# untitled.net
KiCad netlist of a schematic drawn in EAGLE
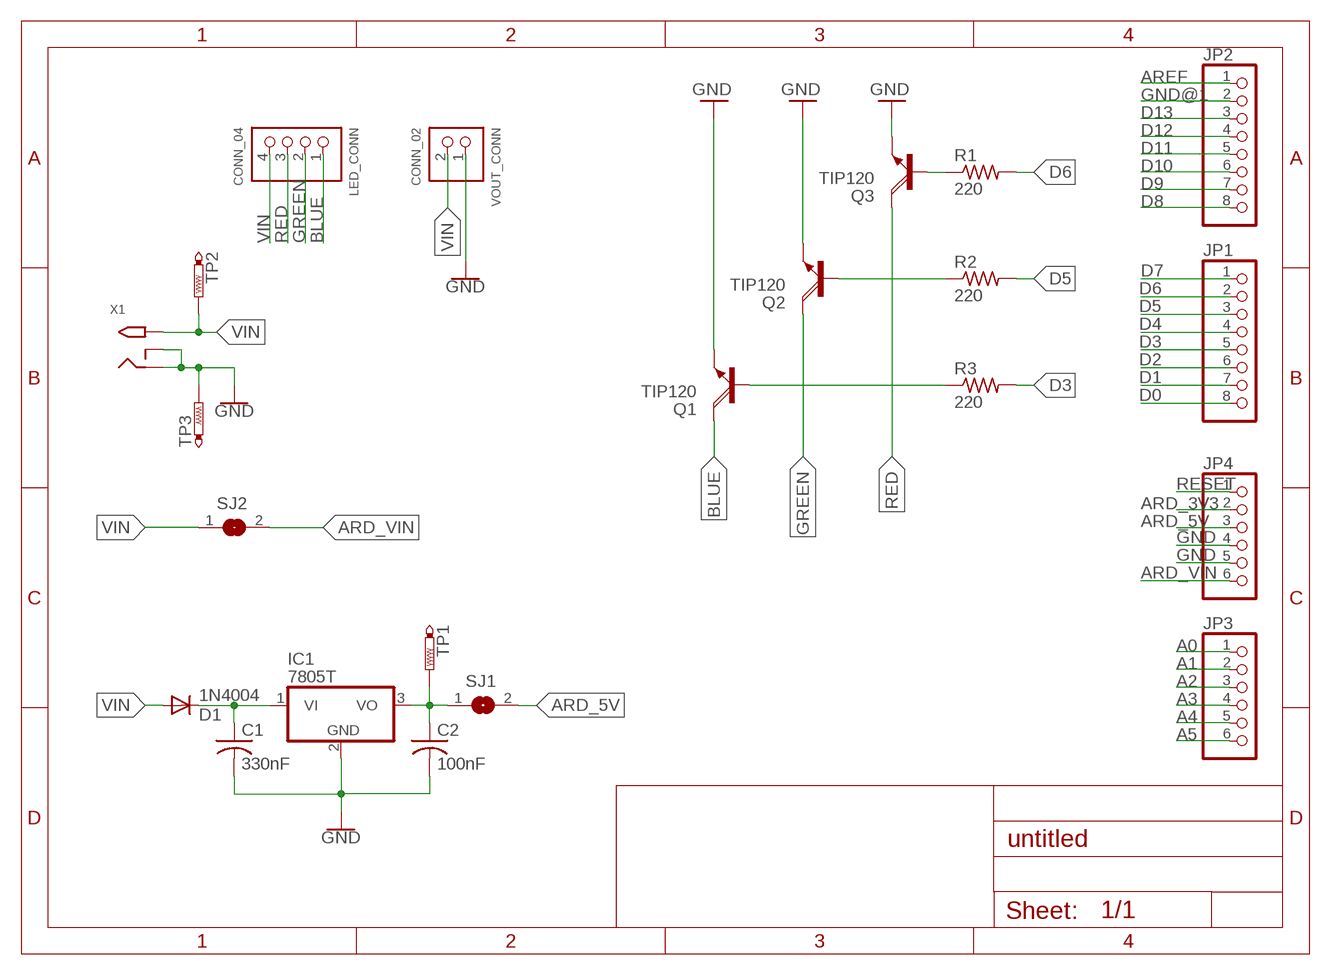
[diagram p0: schematic, sheet 1]

(export (version "E")
  (design (tool "Eeschema 10.0.6"))
  (components
    (comp (ref "C1")
      (value "330nF")
      (footprint "eagle-import:C050-035X075")
      (libsource (lib "eagle-import") (part "C-US050-035X075"))
    )
    (comp (ref "C2")
      (value "100nF")
      (footprint "eagle-import:C050-035X075")
      (libsource (lib "eagle-import") (part "C-US050-035X075"))
    )
    (comp (ref "D1")
      (value "1N4004")
      (footprint "eagle-import:DO41-10")
      (libsource (lib "eagle-import") (part "1N4004"))
    )
    (comp (ref "IC1")
      (value "7805T")
      (footprint "eagle-import:TO220H")
      (libsource (lib "eagle-import") (part "78T05"))
    )
    (comp (ref "JP1")
      (value "PINHD-1X8")
      (footprint "eagle-import:1X08")
      (libsource (lib "eagle-import") (part "PINHD-1X8"))
    )
    (comp (ref "JP2")
      (value "PINHD-1X8")
      (footprint "eagle-import:1X08")
      (libsource (lib "eagle-import") (part "PINHD-1X8"))
    )
    (comp (ref "JP3")
      (value "PINHD-1X6")
      (footprint "eagle-import:1X06")
      (libsource (lib "eagle-import") (part "PINHD-1X6"))
    )
    (comp (ref "JP4")
      (value "PINHD-1X6")
      (footprint "eagle-import:1X06")
      (libsource (lib "eagle-import") (part "PINHD-1X6"))
    )
    (comp (ref "LED_CONN")
      (value "CONN_04")
      (footprint "eagle-import:SCREWTERMINAL-5MM-4")
      (libsource (lib "eagle-import") (part "CONN_04"))
    )
    (comp (ref "Q1")
      (value "TIP120")
      (footprint "eagle-import:TO220AH")
      (libsource (lib "eagle-import") (part "TIP120"))
    )
    (comp (ref "Q2")
      (value "TIP120")
      (footprint "eagle-import:TO220AH")
      (libsource (lib "eagle-import") (part "TIP120"))
    )
    (comp (ref "Q3")
      (value "TIP120")
      (footprint "eagle-import:TO220AH")
      (libsource (lib "eagle-import") (part "TIP120"))
    )
    (comp (ref "R1")
      (value "220")
      (footprint "eagle-import:0207_9")
      (libsource (lib "eagle-import") (part "R-US_0207/9"))
    )
    (comp (ref "R2")
      (value "220")
      (footprint "eagle-import:0207_9")
      (libsource (lib "eagle-import") (part "R-US_0207/9"))
    )
    (comp (ref "R3")
      (value "220")
      (footprint "eagle-import:0207_9")
      (libsource (lib "eagle-import") (part "R-US_0207/9"))
    )
    (comp (ref "SJ1") (value "SJ") (footprint "eagle-import:SJ") (libsource (lib "eagle-import") (part "SJ")))
    (comp (ref "SJ2") (value "SJ") (footprint "eagle-import:SJ") (libsource (lib "eagle-import") (part "SJ")))
    (comp (ref "TP1")
      (value "PTR1B1,27")
      (footprint "eagle-import:B1,27")
      (libsource (lib "eagle-import") (part "PTR1B1,27"))
    )
    (comp (ref "TP2")
      (value "PTR1B1,27")
      (footprint "eagle-import:B1,27")
      (libsource (lib "eagle-import") (part "PTR1B1,27"))
    )
    (comp (ref "TP3")
      (value "PTR1B1,27")
      (footprint "eagle-import:B1,27")
      (libsource (lib "eagle-import") (part "PTR1B1,27"))
    )
    (comp (ref "VOUT_CONN")
      (value "CONN_02")
      (footprint "eagle-import:SCREWTERMINAL-5MM-2")
      (libsource (lib "eagle-import") (part "CONN_02"))
    )
    (comp (ref "X1")
      (value "2.1MMJACKTHM")
      (footprint "eagle-import:PJ-102A")
      (libsource (lib "eagle-import") (part "2.1MMJACKTHM"))
    )
  )
  (nets
    (net (code "1") (name "/A0") (class "Default")
      (node (ref "JP3") (pin "1") (pinfunction "1_1") (pintype "passive"))
    )
    (net (code "2") (name "/A1") (class "Default")
      (node (ref "JP3") (pin "2") (pinfunction "2_2") (pintype "passive"))
    )
    (net (code "3") (name "/A2") (class "Default")
      (node (ref "JP3") (pin "3") (pinfunction "3_3") (pintype "passive"))
    )
    (net (code "4") (name "/A3") (class "Default")
      (node (ref "JP3") (pin "4") (pinfunction "4_4") (pintype "passive"))
    )
    (net (code "5") (name "/A4") (class "Default")
      (node (ref "JP3") (pin "5") (pinfunction "5_5") (pintype "passive"))
    )
    (net (code "6") (name "/A5") (class "Default")
      (node (ref "JP3") (pin "6") (pinfunction "6_6") (pintype "passive"))
    )
    (net (code "7") (name "/ARD_3V3") (class "Default")
      (node (ref "JP4") (pin "2") (pinfunction "2_2") (pintype "passive"))
    )
    (net (code "8") (name "/AREF") (class "Default")
      (node (ref "JP2") (pin "1") (pinfunction "1_1") (pintype "passive"))
    )
    (net (code "9") (name "/D0") (class "Default")
      (node (ref "JP1") (pin "8") (pinfunction "8_8") (pintype "passive"))
    )
    (net (code "10") (name "/D1") (class "Default")
      (node (ref "JP1") (pin "7") (pinfunction "7_7") (pintype "passive"))
    )
    (net (code "11") (name "/D2") (class "Default")
      (node (ref "JP1") (pin "6") (pinfunction "6_6") (pintype "passive"))
    )
    (net (code "12") (name "/D4") (class "Default")
      (node (ref "JP1") (pin "4") (pinfunction "4_4") (pintype "passive"))
    )
    (net (code "13") (name "/D7") (class "Default")
      (node (ref "JP1") (pin "1") (pinfunction "1_1") (pintype "passive"))
    )
    (net (code "14") (name "/D8") (class "Default")
      (node (ref "JP2") (pin "8") (pinfunction "8_8") (pintype "passive"))
    )
    (net (code "15") (name "/D9") (class "Default")
      (node (ref "JP2") (pin "7") (pinfunction "7_7") (pintype "passive"))
    )
    (net (code "16") (name "/D10") (class "Default")
      (node (ref "JP2") (pin "6") (pinfunction "6_6") (pintype "passive"))
    )
    (net (code "17") (name "/D11") (class "Default")
      (node (ref "JP2") (pin "5") (pinfunction "5_5") (pintype "passive"))
    )
    (net (code "18") (name "/D12") (class "Default")
      (node (ref "JP2") (pin "4") (pinfunction "4_4") (pintype "passive"))
    )
    (net (code "19") (name "/D13") (class "Default")
      (node (ref "JP2") (pin "3") (pinfunction "3_3") (pintype "passive"))
    )
    (net (code "20") (name "/GND@1") (class "Default")
      (node (ref "JP2") (pin "2") (pinfunction "2_2") (pintype "passive"))
    )
    (net (code "21") (name "/RESET") (class "Default")
      (node (ref "JP4") (pin "1") (pinfunction "1_1") (pintype "passive"))
    )
    (net (code "22") (name "ARD_5V") (class "Default")
      (node (ref "JP4") (pin "3") (pinfunction "3_3") (pintype "passive"))
      (node (ref "SJ1") (pin "2") (pinfunction "2_2") (pintype "passive"))
    )
    (net (code "23") (name "ARD_VIN") (class "Default")
      (node (ref "JP4") (pin "6") (pinfunction "6_6") (pintype "passive"))
      (node (ref "SJ2") (pin "2") (pinfunction "2_2") (pintype "passive"))
    )
    (net (code "24") (name "BLUE") (class "Default")
      (node (ref "LED_CONN") (pin "1") (pinfunction "1_1") (pintype "bidirectional"))
      (node (ref "Q1") (pin "C") (pinfunction "C_C") (pintype "passive"))
    )
    (net (code "25") (name "D3") (class "Default")
      (node (ref "JP1") (pin "5") (pinfunction "5_5") (pintype "passive"))
      (node (ref "R3") (pin "2") (pinfunction "2_2") (pintype "passive"))
    )
    (net (code "26") (name "D5") (class "Default")
      (node (ref "JP1") (pin "3") (pinfunction "3_3") (pintype "passive"))
      (node (ref "R2") (pin "2") (pinfunction "2_2") (pintype "passive"))
    )
    (net (code "27") (name "D6") (class "Default")
      (node (ref "JP1") (pin "2") (pinfunction "2_2") (pintype "passive"))
      (node (ref "R1") (pin "2") (pinfunction "2_2") (pintype "passive"))
    )
    (net (code "28") (name "GND") (class "Default")
      (node (ref "C1") (pin "2") (pinfunction "2_2") (pintype "passive"))
      (node (ref "C2") (pin "2") (pinfunction "2_2") (pintype "passive"))
      (node (ref "IC1") (pin "2") (pinfunction "GND_2") (pintype "passive"))
      (node (ref "JP4") (pin "4") (pinfunction "4_4") (pintype "passive"))
      (node (ref "JP4") (pin "5") (pinfunction "5_5") (pintype "passive"))
      (node (ref "Q1") (pin "E") (pinfunction "E_E") (pintype "passive"))
      (node (ref "Q2") (pin "E") (pinfunction "E_E") (pintype "passive"))
      (node (ref "Q3") (pin "E") (pinfunction "E_E") (pintype "passive"))
      (node (ref "TP3") (pin "TP") (pinfunction "TP_TP") (pintype "input"))
      (node (ref "VOUT_CONN") (pin "1") (pinfunction "1_1") (pintype "bidirectional"))
      (node (ref "X1") (pin "RING") (pinfunction "RING_RING") (pintype "bidirectional"))
      (node (ref "X1") (pin "RING_SW") (pinfunction "RING_SW_RING_SW") (pintype "bidirectional"))
    )
    (net (code "29") (name "GREEN") (class "Default")
      (node (ref "LED_CONN") (pin "2") (pinfunction "2_2") (pintype "bidirectional"))
      (node (ref "Q2") (pin "C") (pinfunction "C_C") (pintype "passive"))
    )
    (net (code "30") (name "Net-(IC1-VI)") (class "Default")
      (node (ref "C1") (pin "1") (pinfunction "1_1") (pintype "passive"))
      (node (ref "D1") (pin "C") (pinfunction "C_C") (pintype "passive"))
      (node (ref "IC1") (pin "1") (pinfunction "VI_1") (pintype "input"))
    )
    (net (code "31") (name "Net-(IC1-VO)") (class "Default")
      (node (ref "C2") (pin "1") (pinfunction "1_1") (pintype "passive"))
      (node (ref "IC1") (pin "3") (pinfunction "VO_3") (pintype "passive"))
      (node (ref "SJ1") (pin "1") (pinfunction "1_1") (pintype "passive"))
      (node (ref "TP1") (pin "TP") (pinfunction "TP_TP") (pintype "input"))
    )
    (net (code "32") (name "Net-(Q1-PadB)") (class "Default")
      (node (ref "Q1") (pin "B") (pinfunction "B_B") (pintype "passive"))
      (node (ref "R3") (pin "1") (pinfunction "1_1") (pintype "passive"))
    )
    (net (code "33") (name "Net-(Q2-PadB)") (class "Default")
      (node (ref "Q2") (pin "B") (pinfunction "B_B") (pintype "passive"))
      (node (ref "R2") (pin "1") (pinfunction "1_1") (pintype "passive"))
    )
    (net (code "34") (name "Net-(Q3-PadB)") (class "Default")
      (node (ref "Q3") (pin "B") (pinfunction "B_B") (pintype "passive"))
      (node (ref "R1") (pin "1") (pinfunction "1_1") (pintype "passive"))
    )
    (net (code "35") (name "RED") (class "Default")
      (node (ref "LED_CONN") (pin "3") (pinfunction "3_3") (pintype "bidirectional"))
      (node (ref "Q3") (pin "C") (pinfunction "C_C") (pintype "passive"))
    )
    (net (code "36") (name "VIN") (class "Default")
      (node (ref "D1") (pin "A") (pinfunction "A_A") (pintype "passive"))
      (node (ref "LED_CONN") (pin "4") (pinfunction "4_4") (pintype "bidirectional"))
      (node (ref "SJ2") (pin "1") (pinfunction "1_1") (pintype "passive"))
      (node (ref "TP2") (pin "TP") (pinfunction "TP_TP") (pintype "input"))
      (node (ref "VOUT_CONN") (pin "2") (pinfunction "2_2") (pintype "bidirectional"))
      (node (ref "X1") (pin "TIP") (pinfunction "TIP_TIP") (pintype "bidirectional"))
    )
  )
)
